# pk4017.net
KiCad netlist of a schematic drawn in EAGLE
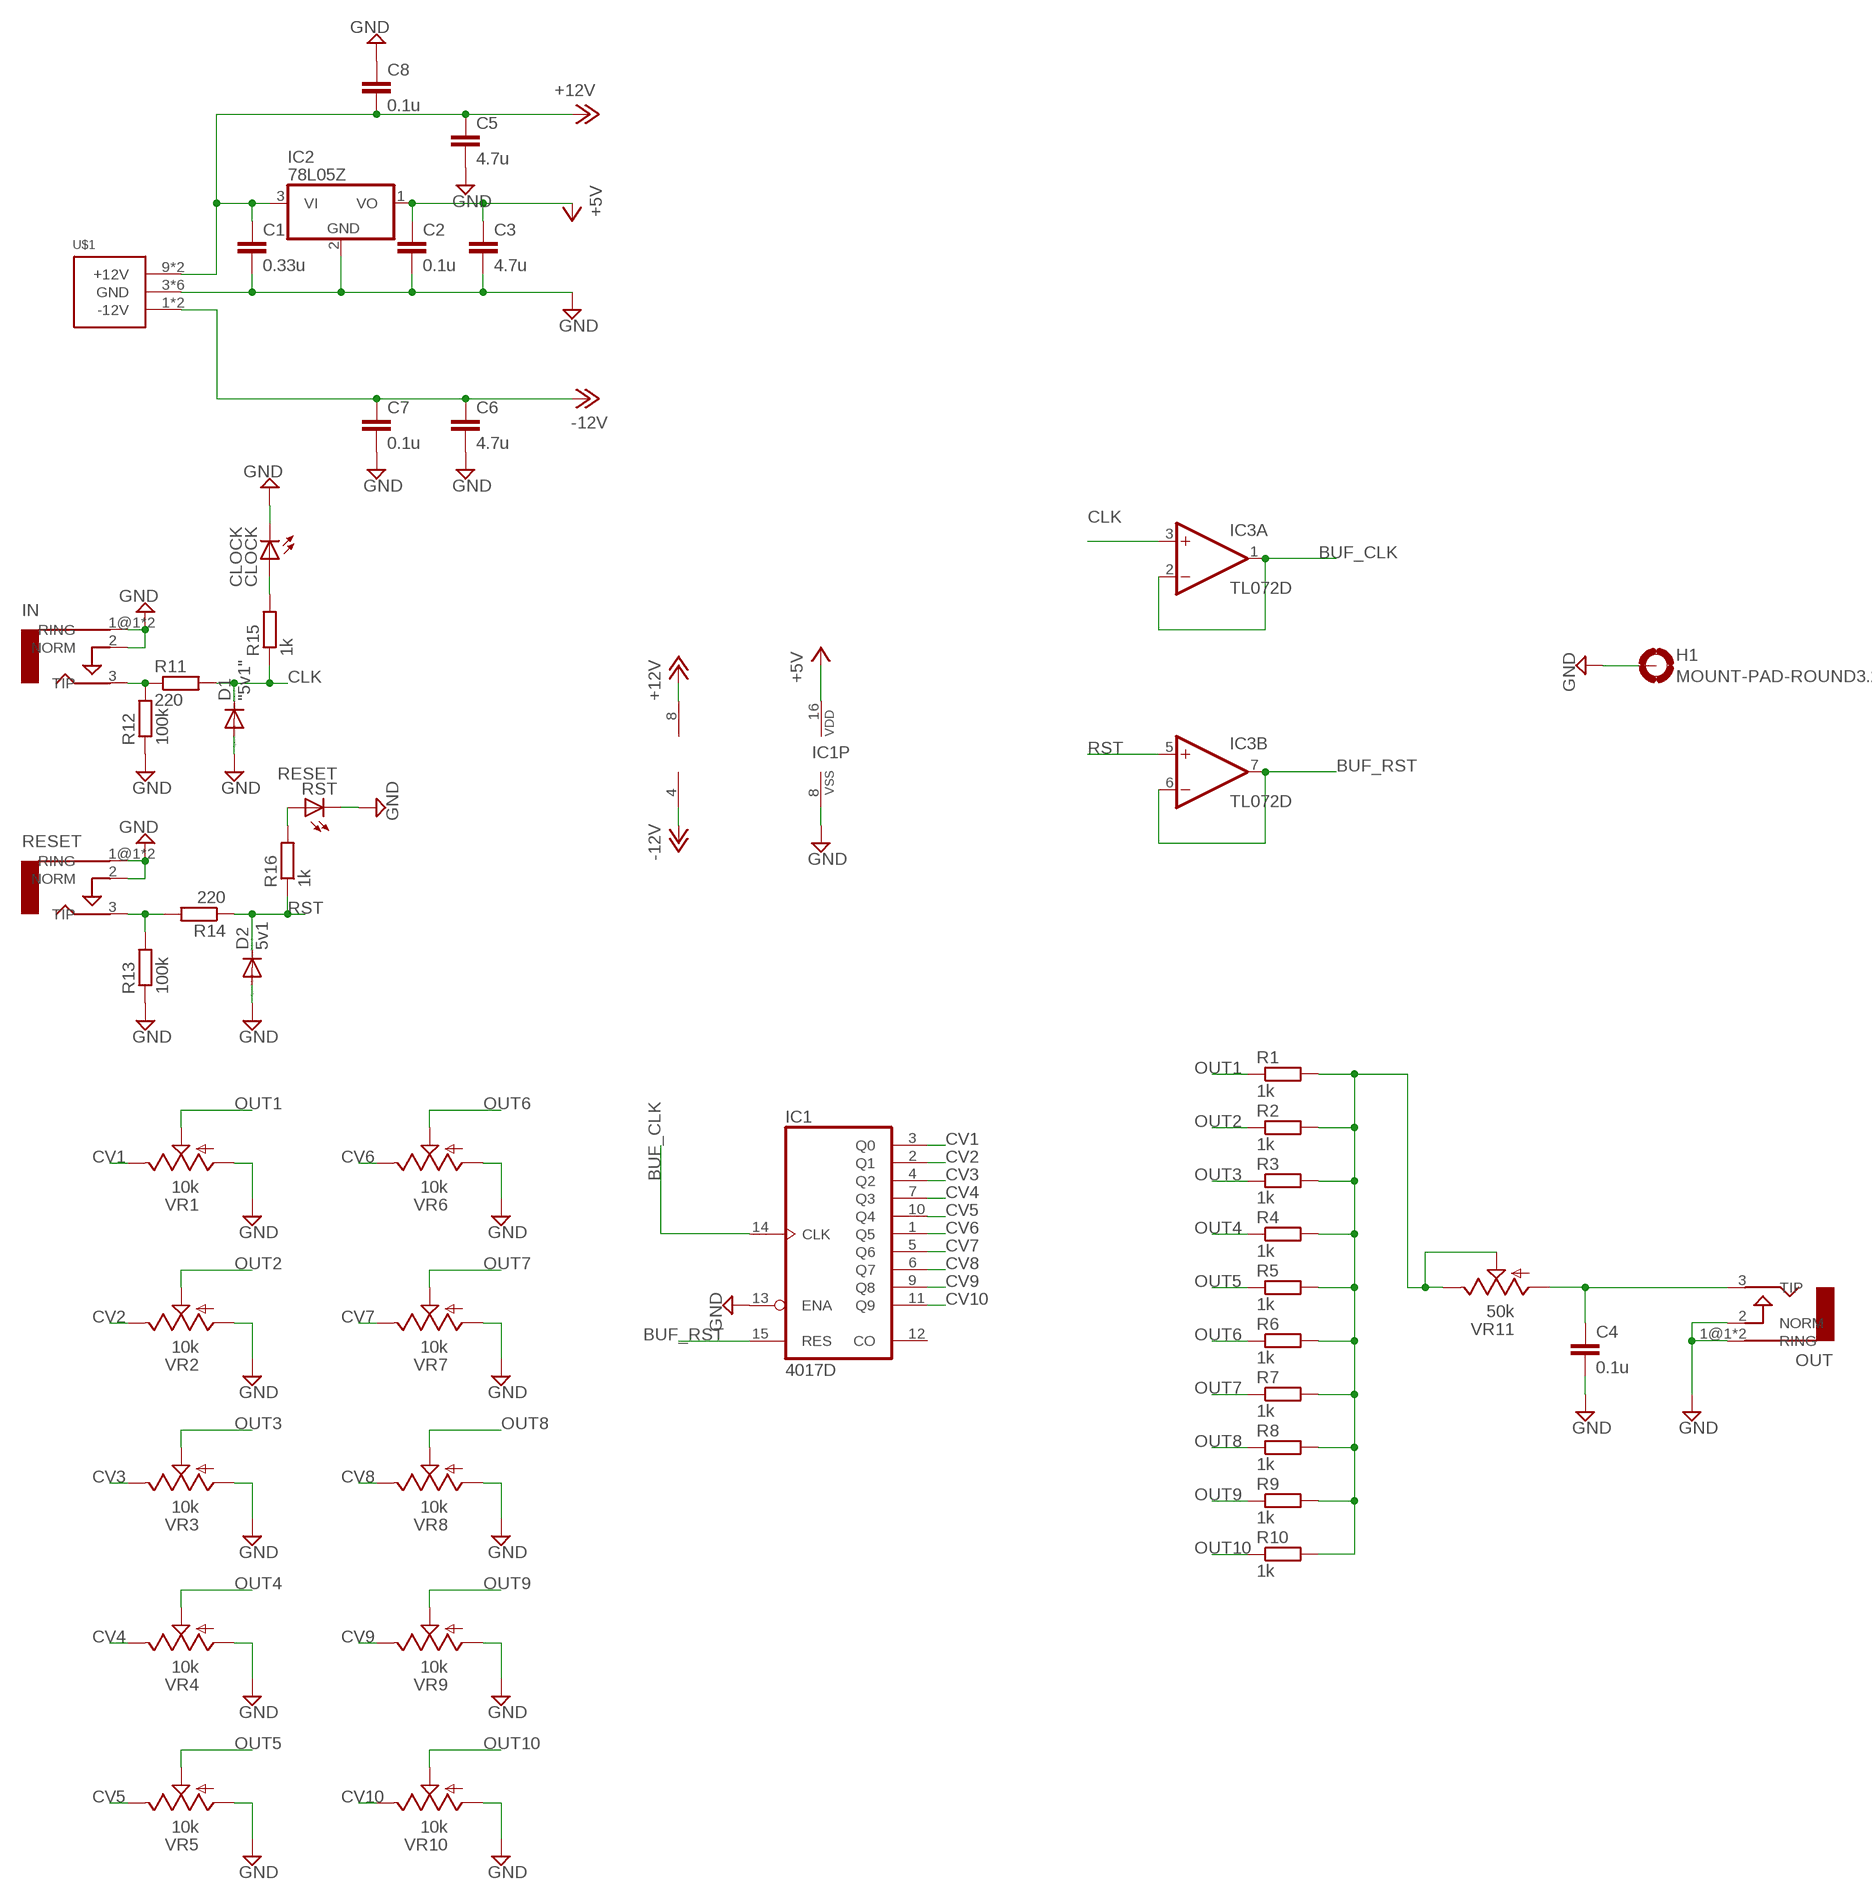
[diagram p0: schematic, sheet 1]

(export (version "E")
  (design (tool "Eeschema 10.0.6"))
  (components
    (comp (ref "C1")
      (value "0.33u")
      (footprint "eagle-import:C0805")
      (libsource (lib "eagle-import") (part "C-EUC0805"))
    )
    (comp (ref "C2")
      (value "0.1u")
      (footprint "eagle-import:C0805")
      (libsource (lib "eagle-import") (part "C-EUC0805"))
    )
    (comp (ref "C3")
      (value "4.7u")
      (footprint "eagle-import:C0805")
      (libsource (lib "eagle-import") (part "C-EUC0805"))
    )
    (comp (ref "C4")
      (value "0.1u")
      (footprint "eagle-import:C050-025X075")
      (libsource (lib "eagle-import") (part "C-EU050-025X075"))
    )
    (comp (ref "C5")
      (value "4.7u")
      (footprint "eagle-import:C0805")
      (libsource (lib "eagle-import") (part "C-EUC0805"))
    )
    (comp (ref "C6")
      (value "4.7u")
      (footprint "eagle-import:C0805")
      (libsource (lib "eagle-import") (part "C-EUC0805"))
    )
    (comp (ref "C7")
      (value "0.1u")
      (footprint "eagle-import:C0805")
      (libsource (lib "eagle-import") (part "C-EUC0805"))
    )
    (comp (ref "C8")
      (value "0.1u")
      (footprint "eagle-import:C0805")
      (libsource (lib "eagle-import") (part "C-EUC0805"))
    )
    (comp (ref "CLOCK")
      (value "CLOCK")
      (footprint "eagle-import:LED3MM")
      (libsource (lib "eagle-import") (part "LED3MM"))
    )
    (comp (ref "D1")
      (value "\"5v1\"")
      (footprint "eagle-import:D-2.5")
      (libsource (lib "eagle-import") (part "DIODE-D-2.5"))
    )
    (comp (ref "D2")
      (value "5v1")
      (footprint "eagle-import:D-2.5")
      (libsource (lib "eagle-import") (part "DIODE-D-2.5"))
    )
    (comp (ref "H1")
      (value "MOUNT-PAD-ROUND3.2")
      (footprint "eagle-import:3,2-PAD")
      (libsource (lib "eagle-import") (part "MOUNT-PAD-ROUND3.2"))
    )
    (comp (ref "IC1")
      (value "4017D")
      (footprint "eagle-import:SO16")
      (libsource (lib "eagle-import") (part "4017D"))
    )
    (comp (ref "IC2")
      (value "78L05Z")
      (footprint "eagle-import:TO92")
      (libsource (lib "eagle-import") (part "78ZL05"))
    )
    (comp (ref "IC3")
      (value "TL072D")
      (footprint "eagle-import:SO08")
      (libsource (lib "eagle-import") (part "TL072D"))
    )
    (comp (ref "IN")
      (value "IN")
      (footprint "eagle-import:ERTHENVAR-JACK")
      (libsource (lib "eagle-import") (part "AUDIO-JACKERTHENVAR"))
    )
    (comp (ref "OUT")
      (value "OUT")
      (footprint "eagle-import:ERTHENVAR-JACK")
      (libsource (lib "eagle-import") (part "AUDIO-JACKERTHENVAR"))
    )
    (comp (ref "R1")
      (value "1k")
      (footprint "eagle-import:R0805")
      (libsource (lib "eagle-import") (part "R-EU_R0805"))
    )
    (comp (ref "R2")
      (value "1k")
      (footprint "eagle-import:R0805")
      (libsource (lib "eagle-import") (part "R-EU_R0805"))
    )
    (comp (ref "R3")
      (value "1k")
      (footprint "eagle-import:R0805")
      (libsource (lib "eagle-import") (part "R-EU_R0805"))
    )
    (comp (ref "R4")
      (value "1k")
      (footprint "eagle-import:R0805")
      (libsource (lib "eagle-import") (part "R-EU_R0805"))
    )
    (comp (ref "R5")
      (value "1k")
      (footprint "eagle-import:R0805")
      (libsource (lib "eagle-import") (part "R-EU_R0805"))
    )
    (comp (ref "R6")
      (value "1k")
      (footprint "eagle-import:R0805")
      (libsource (lib "eagle-import") (part "R-EU_R0805"))
    )
    (comp (ref "R7")
      (value "1k")
      (footprint "eagle-import:R0805")
      (libsource (lib "eagle-import") (part "R-EU_R0805"))
    )
    (comp (ref "R8")
      (value "1k")
      (footprint "eagle-import:R0805")
      (libsource (lib "eagle-import") (part "R-EU_R0805"))
    )
    (comp (ref "R9")
      (value "1k")
      (footprint "eagle-import:R0805")
      (libsource (lib "eagle-import") (part "R-EU_R0805"))
    )
    (comp (ref "R10")
      (value "1k")
      (footprint "eagle-import:R0805")
      (libsource (lib "eagle-import") (part "R-EU_R0805"))
    )
    (comp (ref "R11")
      (value "220")
      (footprint "eagle-import:R0805")
      (libsource (lib "eagle-import") (part "R-EU_R0805"))
    )
    (comp (ref "R12")
      (value "100k")
      (footprint "eagle-import:R0805")
      (libsource (lib "eagle-import") (part "R-EU_R0805"))
    )
    (comp (ref "R13")
      (value "100k")
      (footprint "eagle-import:R0805")
      (libsource (lib "eagle-import") (part "R-EU_R0805"))
    )
    (comp (ref "R14")
      (value "220")
      (footprint "eagle-import:R0805")
      (libsource (lib "eagle-import") (part "R-EU_R0805"))
    )
    (comp (ref "R15")
      (value "1k")
      (footprint "eagle-import:R0805")
      (libsource (lib "eagle-import") (part "R-EU_R0805"))
    )
    (comp (ref "R16")
      (value "1k")
      (footprint "eagle-import:R0805")
      (libsource (lib "eagle-import") (part "R-EU_R0805"))
    )
    (comp (ref "RESET")
      (value "RESET")
      (footprint "eagle-import:ERTHENVAR-JACK")
      (libsource (lib "eagle-import") (part "AUDIO-JACKERTHENVAR"))
    )
    (comp (ref "RST")
      (value "RESET")
      (footprint "eagle-import:LED3MM")
      (libsource (lib "eagle-import") (part "LED3MM"))
    )
    (comp (ref "U$1")
      (value "POWER_SIMPLE10")
      (footprint "eagle-import:POWER_10")
      (libsource (lib "eagle-import") (part "POWER_SIMPLE10"))
    )
    (comp (ref "VR1")
      (value "10k")
      (footprint "eagle-import:9MM_SNAP-IN_POT")
      (libsource (lib "eagle-import") (part "9MM_SNAP-IN_POT_"))
    )
    (comp (ref "VR2")
      (value "10k")
      (footprint "eagle-import:9MM_SNAP-IN_POT")
      (libsource (lib "eagle-import") (part "9MM_SNAP-IN_POT_"))
    )
    (comp (ref "VR3")
      (value "10k")
      (footprint "eagle-import:9MM_SNAP-IN_POT")
      (libsource (lib "eagle-import") (part "9MM_SNAP-IN_POT_"))
    )
    (comp (ref "VR4")
      (value "10k")
      (footprint "eagle-import:9MM_SNAP-IN_POT")
      (libsource (lib "eagle-import") (part "9MM_SNAP-IN_POT_"))
    )
    (comp (ref "VR5")
      (value "10k")
      (footprint "eagle-import:9MM_SNAP-IN_POT")
      (libsource (lib "eagle-import") (part "9MM_SNAP-IN_POT_"))
    )
    (comp (ref "VR6")
      (value "10k")
      (footprint "eagle-import:9MM_SNAP-IN_POT")
      (libsource (lib "eagle-import") (part "9MM_SNAP-IN_POT_"))
    )
    (comp (ref "VR7")
      (value "10k")
      (footprint "eagle-import:9MM_SNAP-IN_POT")
      (libsource (lib "eagle-import") (part "9MM_SNAP-IN_POT_"))
    )
    (comp (ref "VR8")
      (value "10k")
      (footprint "eagle-import:9MM_SNAP-IN_POT")
      (libsource (lib "eagle-import") (part "9MM_SNAP-IN_POT_"))
    )
    (comp (ref "VR9")
      (value "10k")
      (footprint "eagle-import:9MM_SNAP-IN_POT")
      (libsource (lib "eagle-import") (part "9MM_SNAP-IN_POT_"))
    )
    (comp (ref "VR10")
      (value "10k")
      (footprint "eagle-import:9MM_SNAP-IN_POT")
      (libsource (lib "eagle-import") (part "9MM_SNAP-IN_POT_"))
    )
    (comp (ref "VR11")
      (value "50k")
      (footprint "eagle-import:9MM_SNAP-IN_POT")
      (libsource (lib "eagle-import") (part "9MM_SNAP-IN_POT_"))
    )
  )
  (nets
    (net (code "1") (name "+5V") (class "Default")
      (node (ref "C2") (pin "1") (pinfunction "1_1") (pintype "passive"))
      (node (ref "C3") (pin "1") (pinfunction "1_1") (pintype "passive"))
      (node (ref "IC1") (pin "16") (pinfunction "VDD_16") (pintype "power_in"))
      (node (ref "IC2") (pin "1") (pinfunction "VO_1") (pintype "passive"))
    )
    (net (code "2") (name "+12V") (class "Default")
      (node (ref "C1") (pin "1") (pinfunction "1_1") (pintype "passive"))
      (node (ref "C5") (pin "1") (pinfunction "1_1") (pintype "passive"))
      (node (ref "C8") (pin "2") (pinfunction "2_2") (pintype "passive"))
      (node (ref "IC2") (pin "3") (pinfunction "VI_3") (pintype "input"))
      (node (ref "IC3") (pin "8") (pinfunction "V+_8") (pintype "power_in"))
      (node (ref "U$1") (pin "10") (pinfunction "+12V_10") (pintype "bidirectional"))
      (node (ref "U$1") (pin "9") (pinfunction "+12V_9") (pintype "bidirectional"))
    )
    (net (code "3") (name "-12V") (class "Default")
      (node (ref "C6") (pin "1") (pinfunction "1_1") (pintype "passive"))
      (node (ref "C7") (pin "1") (pinfunction "1_1") (pintype "passive"))
      (node (ref "IC3") (pin "4") (pinfunction "V-_4") (pintype "power_in"))
      (node (ref "U$1") (pin "1") (pinfunction "-12V_1") (pintype "bidirectional"))
      (node (ref "U$1") (pin "2") (pinfunction "-12V_2") (pintype "bidirectional"))
    )
    (net (code "4") (name "/BUF_CLK") (class "Default")
      (node (ref "IC1") (pin "14") (pinfunction "CLK_14") (pintype "input"))
      (node (ref "IC3") (pin "1") (pinfunction "OUT_1") (pintype "output"))
      (node (ref "IC3") (pin "2") (pinfunction "-IN_2") (pintype "input"))
    )
    (net (code "5") (name "/BUF_RST") (class "Default")
      (node (ref "IC1") (pin "15") (pinfunction "RES_15") (pintype "input"))
      (node (ref "IC3") (pin "6") (pinfunction "-IN_6") (pintype "input"))
      (node (ref "IC3") (pin "7") (pinfunction "OUT_7") (pintype "output"))
    )
    (net (code "6") (name "/CLK") (class "Default")
      (node (ref "D1") (pin "C") (pinfunction "C_C") (pintype "passive"))
      (node (ref "IC3") (pin "3") (pinfunction "+IN_3") (pintype "input"))
      (node (ref "R11") (pin "2") (pinfunction "2_2") (pintype "passive"))
      (node (ref "R15") (pin "1") (pinfunction "1_1") (pintype "passive"))
    )
    (net (code "7") (name "/CV1") (class "Default")
      (node (ref "IC1") (pin "3") (pinfunction "Q0_3") (pintype "output"))
      (node (ref "VR1") (pin "3") (pinfunction "E_3") (pintype "passive"))
    )
    (net (code "8") (name "/CV2") (class "Default")
      (node (ref "IC1") (pin "2") (pinfunction "Q1_2") (pintype "output"))
      (node (ref "VR2") (pin "3") (pinfunction "E_3") (pintype "passive"))
    )
    (net (code "9") (name "/CV3") (class "Default")
      (node (ref "IC1") (pin "4") (pinfunction "Q2_4") (pintype "output"))
      (node (ref "VR3") (pin "3") (pinfunction "E_3") (pintype "passive"))
    )
    (net (code "10") (name "/CV4") (class "Default")
      (node (ref "IC1") (pin "7") (pinfunction "Q3_7") (pintype "output"))
      (node (ref "VR4") (pin "3") (pinfunction "E_3") (pintype "passive"))
    )
    (net (code "11") (name "/CV5") (class "Default")
      (node (ref "IC1") (pin "10") (pinfunction "Q4_10") (pintype "output"))
      (node (ref "VR5") (pin "3") (pinfunction "E_3") (pintype "passive"))
    )
    (net (code "12") (name "/CV6") (class "Default")
      (node (ref "IC1") (pin "1") (pinfunction "Q5_1") (pintype "output"))
      (node (ref "VR6") (pin "3") (pinfunction "E_3") (pintype "passive"))
    )
    (net (code "13") (name "/CV7") (class "Default")
      (node (ref "IC1") (pin "5") (pinfunction "Q6_5") (pintype "output"))
      (node (ref "VR7") (pin "3") (pinfunction "E_3") (pintype "passive"))
    )
    (net (code "14") (name "/CV8") (class "Default")
      (node (ref "IC1") (pin "6") (pinfunction "Q7_6") (pintype "output"))
      (node (ref "VR8") (pin "3") (pinfunction "E_3") (pintype "passive"))
    )
    (net (code "15") (name "/CV9") (class "Default")
      (node (ref "IC1") (pin "9") (pinfunction "Q8_9") (pintype "output"))
      (node (ref "VR9") (pin "3") (pinfunction "E_3") (pintype "passive"))
    )
    (net (code "16") (name "/CV10") (class "Default")
      (node (ref "IC1") (pin "11") (pinfunction "Q9_11") (pintype "output"))
      (node (ref "VR10") (pin "3") (pinfunction "E_3") (pintype "passive"))
    )
    (net (code "17") (name "/OUT1") (class "Default")
      (node (ref "R1") (pin "1") (pinfunction "1_1") (pintype "passive"))
      (node (ref "VR1") (pin "2") (pinfunction "S_2") (pintype "passive"))
    )
    (net (code "18") (name "/OUT2") (class "Default")
      (node (ref "R2") (pin "1") (pinfunction "1_1") (pintype "passive"))
      (node (ref "VR2") (pin "2") (pinfunction "S_2") (pintype "passive"))
    )
    (net (code "19") (name "/OUT3") (class "Default")
      (node (ref "R3") (pin "1") (pinfunction "1_1") (pintype "passive"))
      (node (ref "VR3") (pin "2") (pinfunction "S_2") (pintype "passive"))
    )
    (net (code "20") (name "/OUT4") (class "Default")
      (node (ref "R4") (pin "1") (pinfunction "1_1") (pintype "passive"))
      (node (ref "VR4") (pin "2") (pinfunction "S_2") (pintype "passive"))
    )
    (net (code "21") (name "/OUT5") (class "Default")
      (node (ref "R5") (pin "1") (pinfunction "1_1") (pintype "passive"))
      (node (ref "VR5") (pin "2") (pinfunction "S_2") (pintype "passive"))
    )
    (net (code "22") (name "/OUT6") (class "Default")
      (node (ref "R6") (pin "1") (pinfunction "1_1") (pintype "passive"))
      (node (ref "VR6") (pin "2") (pinfunction "S_2") (pintype "passive"))
    )
    (net (code "23") (name "/OUT7") (class "Default")
      (node (ref "R7") (pin "1") (pinfunction "1_1") (pintype "passive"))
      (node (ref "VR7") (pin "2") (pinfunction "S_2") (pintype "passive"))
    )
    (net (code "24") (name "/OUT8") (class "Default")
      (node (ref "R8") (pin "1") (pinfunction "1_1") (pintype "passive"))
      (node (ref "VR8") (pin "2") (pinfunction "S_2") (pintype "passive"))
    )
    (net (code "25") (name "/OUT9") (class "Default")
      (node (ref "R9") (pin "1") (pinfunction "1_1") (pintype "passive"))
      (node (ref "VR9") (pin "2") (pinfunction "S_2") (pintype "passive"))
    )
    (net (code "26") (name "/OUT10") (class "Default")
      (node (ref "R10") (pin "1") (pinfunction "1_1") (pintype "passive"))
      (node (ref "VR10") (pin "2") (pinfunction "S_2") (pintype "passive"))
    )
    (net (code "27") (name "/RST") (class "Default")
      (node (ref "D2") (pin "C") (pinfunction "C_C") (pintype "passive"))
      (node (ref "IC3") (pin "5") (pinfunction "+IN_5") (pintype "input"))
      (node (ref "R14") (pin "1") (pinfunction "1_1") (pintype "passive"))
      (node (ref "R16") (pin "1") (pinfunction "1_1") (pintype "passive"))
    )
    (net (code "28") (name "GND") (class "Default")
      (node (ref "C1") (pin "2") (pinfunction "2_2") (pintype "passive"))
      (node (ref "C2") (pin "2") (pinfunction "2_2") (pintype "passive"))
      (node (ref "C3") (pin "2") (pinfunction "2_2") (pintype "passive"))
      (node (ref "C4") (pin "2") (pinfunction "2_2") (pintype "passive"))
      (node (ref "C5") (pin "2") (pinfunction "2_2") (pintype "passive"))
      (node (ref "C6") (pin "2") (pinfunction "2_2") (pintype "passive"))
      (node (ref "C7") (pin "2") (pinfunction "2_2") (pintype "passive"))
      (node (ref "C8") (pin "1") (pinfunction "1_1") (pintype "passive"))
      (node (ref "CLOCK") (pin "K") (pinfunction "C_K") (pintype "passive"))
      (node (ref "D1") (pin "A") (pinfunction "A_A") (pintype "passive"))
      (node (ref "D2") (pin "A") (pinfunction "A_A") (pintype "passive"))
      (node (ref "H1") (pin "B3,2") (pinfunction "MOUNT_B3,2") (pintype "passive"))
      (node (ref "IC1") (pin "13") (pinfunction "ENA_13") (pintype "input"))
      (node (ref "IC1") (pin "8") (pinfunction "VSS_8") (pintype "power_in"))
      (node (ref "IC2") (pin "2") (pinfunction "GND_2") (pintype "passive"))
      (node (ref "IN") (pin "1@1") (pinfunction "RING_1@1") (pintype "bidirectional"))
      (node (ref "IN") (pin "1@2") (pinfunction "RING_1@2") (pintype "bidirectional"))
      (node (ref "IN") (pin "2") (pinfunction "NORM_2") (pintype "bidirectional"))
      (node (ref "OUT") (pin "1@1") (pinfunction "RING_1@1") (pintype "bidirectional"))
      (node (ref "OUT") (pin "1@2") (pinfunction "RING_1@2") (pintype "bidirectional"))
      (node (ref "OUT") (pin "2") (pinfunction "NORM_2") (pintype "bidirectional"))
      (node (ref "R12") (pin "1") (pinfunction "1_1") (pintype "passive"))
      (node (ref "R13") (pin "1") (pinfunction "1_1") (pintype "passive"))
      (node (ref "RESET") (pin "1@1") (pinfunction "RING_1@1") (pintype "bidirectional"))
      (node (ref "RESET") (pin "1@2") (pinfunction "RING_1@2") (pintype "bidirectional"))
      (node (ref "RESET") (pin "2") (pinfunction "NORM_2") (pintype "bidirectional"))
      (node (ref "RST") (pin "K") (pinfunction "C_K") (pintype "passive"))
      (node (ref "U$1") (pin "3") (pinfunction "GND_3") (pintype "bidirectional"))
      (node (ref "U$1") (pin "4") (pinfunction "GND_4") (pintype "bidirectional"))
      (node (ref "U$1") (pin "5") (pinfunction "GND_5") (pintype "bidirectional"))
      (node (ref "U$1") (pin "6") (pinfunction "GND_6") (pintype "bidirectional"))
      (node (ref "U$1") (pin "7") (pinfunction "GND_7") (pintype "bidirectional"))
      (node (ref "U$1") (pin "8") (pinfunction "GND_8") (pintype "bidirectional"))
      (node (ref "VR1") (pin "1") (pinfunction "A_1") (pintype "passive"))
      (node (ref "VR10") (pin "1") (pinfunction "A_1") (pintype "passive"))
      (node (ref "VR2") (pin "1") (pinfunction "A_1") (pintype "passive"))
      (node (ref "VR3") (pin "1") (pinfunction "A_1") (pintype "passive"))
      (node (ref "VR4") (pin "1") (pinfunction "A_1") (pintype "passive"))
      (node (ref "VR5") (pin "1") (pinfunction "A_1") (pintype "passive"))
      (node (ref "VR6") (pin "1") (pinfunction "A_1") (pintype "passive"))
      (node (ref "VR7") (pin "1") (pinfunction "A_1") (pintype "passive"))
      (node (ref "VR8") (pin "1") (pinfunction "A_1") (pintype "passive"))
      (node (ref "VR9") (pin "1") (pinfunction "A_1") (pintype "passive"))
    )
    (net (code "29") (name "Net-(CLOCK-PadA)") (class "Default")
      (node (ref "CLOCK") (pin "A") (pinfunction "A_A") (pintype "passive"))
      (node (ref "R15") (pin "2") (pinfunction "2_2") (pintype "passive"))
    )
    (net (code "30") (name "Net-(IN-TIP)") (class "Default")
      (node (ref "IN") (pin "3") (pinfunction "TIP_3") (pintype "bidirectional"))
      (node (ref "R11") (pin "1") (pinfunction "1_1") (pintype "passive"))
      (node (ref "R12") (pin "2") (pinfunction "2_2") (pintype "passive"))
    )
    (net (code "31") (name "Net-(OUT-TIP)") (class "Default")
      (node (ref "C4") (pin "1") (pinfunction "1_1") (pintype "passive"))
      (node (ref "OUT") (pin "3") (pinfunction "TIP_3") (pintype "bidirectional"))
      (node (ref "VR11") (pin "1") (pinfunction "A_1") (pintype "passive"))
    )
    (net (code "32") (name "Net-(R16-Pad2)") (class "Default")
      (node (ref "R16") (pin "2") (pinfunction "2_2") (pintype "passive"))
      (node (ref "RST") (pin "A") (pinfunction "A_A") (pintype "passive"))
    )
    (net (code "33") (name "Net-(RESET-TIP)") (class "Default")
      (node (ref "R13") (pin "2") (pinfunction "2_2") (pintype "passive"))
      (node (ref "R14") (pin "2") (pinfunction "2_2") (pintype "passive"))
      (node (ref "RESET") (pin "3") (pinfunction "TIP_3") (pintype "bidirectional"))
    )
    (net (code "34") (name "Net-(VR11-E)") (class "Default")
      (node (ref "R1") (pin "2") (pinfunction "2_2") (pintype "passive"))
      (node (ref "R10") (pin "2") (pinfunction "2_2") (pintype "passive"))
      (node (ref "R2") (pin "2") (pinfunction "2_2") (pintype "passive"))
      (node (ref "R3") (pin "2") (pinfunction "2_2") (pintype "passive"))
      (node (ref "R4") (pin "2") (pinfunction "2_2") (pintype "passive"))
      (node (ref "R5") (pin "2") (pinfunction "2_2") (pintype "passive"))
      (node (ref "R6") (pin "2") (pinfunction "2_2") (pintype "passive"))
      (node (ref "R7") (pin "2") (pinfunction "2_2") (pintype "passive"))
      (node (ref "R8") (pin "2") (pinfunction "2_2") (pintype "passive"))
      (node (ref "R9") (pin "2") (pinfunction "2_2") (pintype "passive"))
      (node (ref "VR11") (pin "2") (pinfunction "S_2") (pintype "passive"))
      (node (ref "VR11") (pin "3") (pinfunction "E_3") (pintype "passive"))
    )
    (net (code "35") (name "unconnected-(IC1A-CO-Pad12)") (class "Default")
      (node (ref "IC1") (pin "12") (pinfunction "CO_12") (pintype "output"))
    )
  )
)
